# relay_AZ850P2_THT.net
KiCad netlist of a schematic drawn in EAGLE
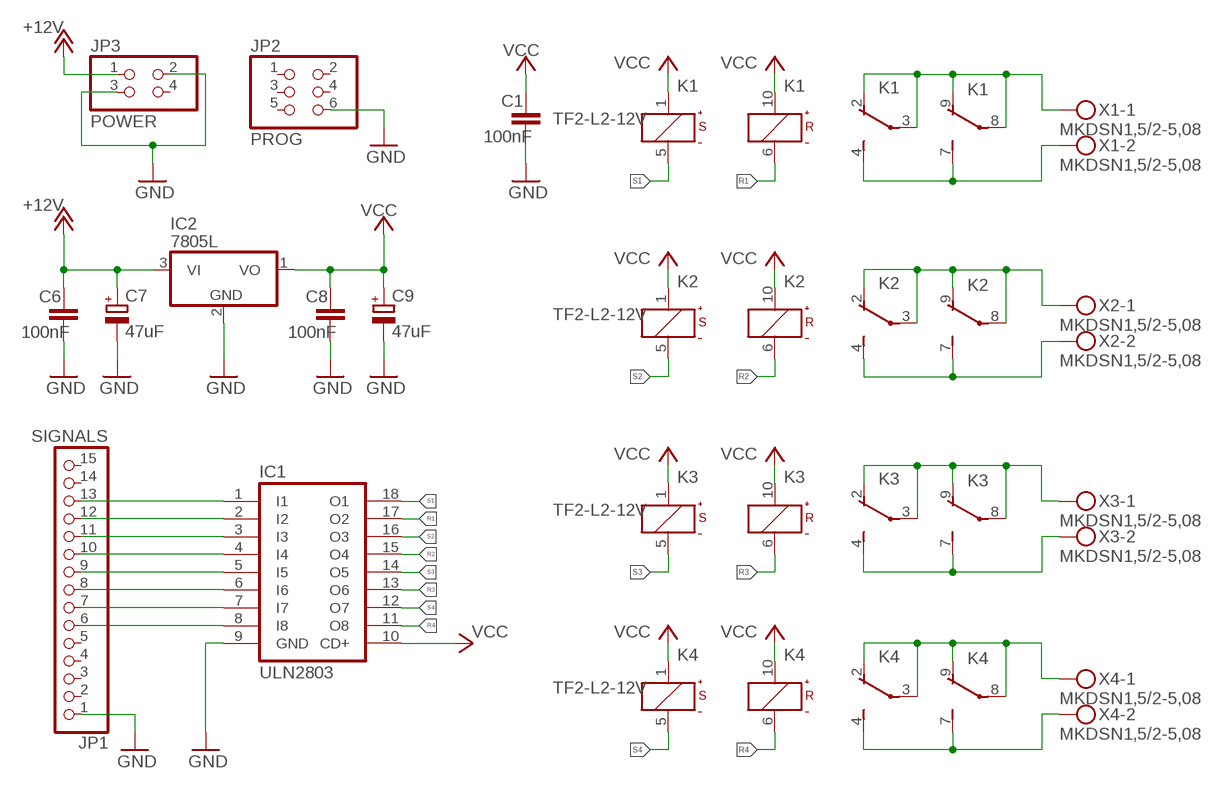
[diagram p0: schematic, sheet 1]

(export (version "E")
  (design (tool "Eeschema 10.0.6"))
  (components
    (comp (ref "C1")
      (value "100nF")
      (footprint "eagle-import:C025-025X050")
      (libsource (lib "eagle-import") (part "C-EU025-025X050"))
    )
    (comp (ref "C6")
      (value "100nF")
      (footprint "eagle-import:C025-025X050")
      (libsource (lib "eagle-import") (part "C-EU025-025X050"))
    )
    (comp (ref "C7")
      (value "47uF")
      (footprint "eagle-import:E2,5-6")
      (libsource (lib "eagle-import") (part "CPOL-EUE2.5-6"))
    )
    (comp (ref "C8")
      (value "100nF")
      (footprint "eagle-import:C025-025X050")
      (libsource (lib "eagle-import") (part "C-EU025-025X050"))
    )
    (comp (ref "C9")
      (value "47uF")
      (footprint "eagle-import:E2,5-6")
      (libsource (lib "eagle-import") (part "CPOL-EUE2.5-6"))
    )
    (comp (ref "IC1")
      (value "ULN2803")
      (footprint "eagle-import:DIL18")
      (libsource (lib "eagle-import") (part "ULN2803A"))
    )
    (comp (ref "IC2")
      (value "7805L")
      (footprint "eagle-import:TO92")
      (libsource (lib "eagle-import") (part "78L05"))
    )
    (comp (ref "JP1")
      (value "SIGNALS")
      (footprint "eagle-import:1X15")
      (libsource (lib "eagle-import") (part "PINHD-1X15"))
    )
    (comp (ref "JP2")
      (value "PROG")
      (footprint "eagle-import:2X03")
      (libsource (lib "eagle-import") (part "PINHD-2X3"))
    )
    (comp (ref "JP3")
      (value "POWER")
      (footprint "eagle-import:2X02")
      (libsource (lib "eagle-import") (part "PINHD-2X2"))
    )
    (comp (ref "K1")
      (value "TF2-L2-12V")
      (footprint "eagle-import:TF2")
      (libsource (lib "eagle-import") (part "TF2-L2-12V"))
    )
    (comp (ref "K2")
      (value "TF2-L2-12V")
      (footprint "eagle-import:TF2")
      (libsource (lib "eagle-import") (part "TF2-L2-12V"))
    )
    (comp (ref "K3")
      (value "TF2-L2-12V")
      (footprint "eagle-import:TF2")
      (libsource (lib "eagle-import") (part "TF2-L2-12V"))
    )
    (comp (ref "K4")
      (value "TF2-L2-12V")
      (footprint "eagle-import:TF2")
      (libsource (lib "eagle-import") (part "TF2-L2-12V"))
    )
    (comp (ref "X1")
      (value "MKDSN1,5/2-5,08")
      (footprint "eagle-import:MKDSN1,5_2-5,08")
      (fields (field (name "MPN") "MKDSN 1,5/2-5.08"))
      (libsource (lib "eagle-import") (part "MKDSN1,5/2-5,08"))
    )
    (comp (ref "X2")
      (value "MKDSN1,5/2-5,08")
      (footprint "eagle-import:MKDSN1,5_2-5,08")
      (fields (field (name "MPN") "MKDSN 1,5/2-5.08"))
      (libsource (lib "eagle-import") (part "MKDSN1,5/2-5,08"))
    )
    (comp (ref "X3")
      (value "MKDSN1,5/2-5,08")
      (footprint "eagle-import:MKDSN1,5_2-5,08")
      (fields (field (name "MPN") "MKDSN 1,5/2-5.08"))
      (libsource (lib "eagle-import") (part "MKDSN1,5/2-5,08"))
    )
    (comp (ref "X4")
      (value "MKDSN1,5/2-5,08")
      (footprint "eagle-import:MKDSN1,5_2-5,08")
      (fields (field (name "MPN") "MKDSN 1,5/2-5.08"))
      (libsource (lib "eagle-import") (part "MKDSN1,5/2-5,08"))
    )
  )
  (nets
    (net (code "1") (name "+12V") (class "Default")
      (node (ref "C6") (pin "1") (pinfunction "1_1") (pintype "passive"))
      (node (ref "C7") (pin "+") (pinfunction "+_+") (pintype "passive"))
      (node (ref "IC2") (pin "3") (pinfunction "VI_3") (pintype "input"))
      (node (ref "JP3") (pin "1") (pinfunction "1_1") (pintype "passive"))
    )
    (net (code "2") (name "GND") (class "Default")
      (node (ref "C1") (pin "2") (pinfunction "2_2") (pintype "passive"))
      (node (ref "C6") (pin "2") (pinfunction "2_2") (pintype "passive"))
      (node (ref "C7") (pin "-") (pinfunction "-_-") (pintype "passive"))
      (node (ref "C8") (pin "2") (pinfunction "2_2") (pintype "passive"))
      (node (ref "C9") (pin "-") (pinfunction "-_-") (pintype "passive"))
      (node (ref "IC1") (pin "9") (pinfunction "GND_9") (pintype "power_in"))
      (node (ref "IC2") (pin "2") (pinfunction "GND_2") (pintype "passive"))
      (node (ref "JP1") (pin "1") (pinfunction "1_1") (pintype "passive"))
      (node (ref "JP2") (pin "6") (pinfunction "6_6") (pintype "passive"))
      (node (ref "JP3") (pin "2") (pinfunction "2_2") (pintype "passive"))
      (node (ref "JP3") (pin "3") (pinfunction "3_3") (pintype "passive"))
    )
    (net (code "3") (name "Net-(IC1-I1)") (class "Default")
      (node (ref "IC1") (pin "1") (pinfunction "I1_1") (pintype "input"))
      (node (ref "JP1") (pin "13") (pinfunction "13_13") (pintype "passive"))
    )
    (net (code "4") (name "Net-(IC1-I2)") (class "Default")
      (node (ref "IC1") (pin "2") (pinfunction "I2_2") (pintype "input"))
      (node (ref "JP1") (pin "12") (pinfunction "12_12") (pintype "passive"))
    )
    (net (code "5") (name "Net-(IC1-I3)") (class "Default")
      (node (ref "IC1") (pin "3") (pinfunction "I3_3") (pintype "input"))
      (node (ref "JP1") (pin "11") (pinfunction "11_11") (pintype "passive"))
    )
    (net (code "6") (name "Net-(IC1-I4)") (class "Default")
      (node (ref "IC1") (pin "4") (pinfunction "I4_4") (pintype "input"))
      (node (ref "JP1") (pin "10") (pinfunction "10_10") (pintype "passive"))
    )
    (net (code "7") (name "Net-(IC1-I5)") (class "Default")
      (node (ref "IC1") (pin "5") (pinfunction "I5_5") (pintype "input"))
      (node (ref "JP1") (pin "9") (pinfunction "9_9") (pintype "passive"))
    )
    (net (code "8") (name "Net-(IC1-I6)") (class "Default")
      (node (ref "IC1") (pin "6") (pinfunction "I6_6") (pintype "input"))
      (node (ref "JP1") (pin "8") (pinfunction "8_8") (pintype "passive"))
    )
    (net (code "9") (name "Net-(IC1-I7)") (class "Default")
      (node (ref "IC1") (pin "7") (pinfunction "I7_7") (pintype "input"))
      (node (ref "JP1") (pin "7") (pinfunction "7_7") (pintype "passive"))
    )
    (net (code "10") (name "Net-(IC1-I8)") (class "Default")
      (node (ref "IC1") (pin "8") (pinfunction "I8_8") (pintype "input"))
      (node (ref "JP1") (pin "6") (pinfunction "6_6") (pintype "passive"))
    )
    (net (code "11") (name "Net-(K1A-O)") (class "Default")
      (node (ref "K1") (pin "2") (pinfunction "O_2") (pintype "passive"))
      (node (ref "K1") (pin "3") (pinfunction "P_3") (pintype "passive"))
      (node (ref "K1") (pin "8") (pinfunction "P_8") (pintype "passive"))
      (node (ref "K1") (pin "9") (pinfunction "O_9") (pintype "passive"))
      (node (ref "X1") (pin "1") (pinfunction "KL_1") (pintype "passive"))
    )
    (net (code "12") (name "Net-(K1A-S)") (class "Default")
      (node (ref "K1") (pin "4") (pinfunction "S_4") (pintype "passive"))
      (node (ref "K1") (pin "7") (pinfunction "S_7") (pintype "passive"))
      (node (ref "X1") (pin "2") (pinfunction "KL_2") (pintype "passive"))
    )
    (net (code "13") (name "Net-(K2A-O)") (class "Default")
      (node (ref "K2") (pin "2") (pinfunction "O_2") (pintype "passive"))
      (node (ref "K2") (pin "3") (pinfunction "P_3") (pintype "passive"))
      (node (ref "K2") (pin "8") (pinfunction "P_8") (pintype "passive"))
      (node (ref "K2") (pin "9") (pinfunction "O_9") (pintype "passive"))
      (node (ref "X2") (pin "1") (pinfunction "KL_1") (pintype "passive"))
    )
    (net (code "14") (name "Net-(K2A-S)") (class "Default")
      (node (ref "K2") (pin "4") (pinfunction "S_4") (pintype "passive"))
      (node (ref "K2") (pin "7") (pinfunction "S_7") (pintype "passive"))
      (node (ref "X2") (pin "2") (pinfunction "KL_2") (pintype "passive"))
    )
    (net (code "15") (name "Net-(K3A-O)") (class "Default")
      (node (ref "K3") (pin "2") (pinfunction "O_2") (pintype "passive"))
      (node (ref "K3") (pin "3") (pinfunction "P_3") (pintype "passive"))
      (node (ref "K3") (pin "8") (pinfunction "P_8") (pintype "passive"))
      (node (ref "K3") (pin "9") (pinfunction "O_9") (pintype "passive"))
      (node (ref "X3") (pin "1") (pinfunction "KL_1") (pintype "passive"))
    )
    (net (code "16") (name "Net-(K3A-S)") (class "Default")
      (node (ref "K3") (pin "4") (pinfunction "S_4") (pintype "passive"))
      (node (ref "K3") (pin "7") (pinfunction "S_7") (pintype "passive"))
      (node (ref "X3") (pin "2") (pinfunction "KL_2") (pintype "passive"))
    )
    (net (code "17") (name "Net-(K4A-O)") (class "Default")
      (node (ref "K4") (pin "2") (pinfunction "O_2") (pintype "passive"))
      (node (ref "K4") (pin "3") (pinfunction "P_3") (pintype "passive"))
      (node (ref "K4") (pin "8") (pinfunction "P_8") (pintype "passive"))
      (node (ref "K4") (pin "9") (pinfunction "O_9") (pintype "passive"))
      (node (ref "X4") (pin "1") (pinfunction "KL_1") (pintype "passive"))
    )
    (net (code "18") (name "Net-(K4A-S)") (class "Default")
      (node (ref "K4") (pin "4") (pinfunction "S_4") (pintype "passive"))
      (node (ref "K4") (pin "7") (pinfunction "S_7") (pintype "passive"))
      (node (ref "X4") (pin "2") (pinfunction "KL_2") (pintype "passive"))
    )
    (net (code "19") (name "R1") (class "Default")
      (node (ref "IC1") (pin "17") (pinfunction "O2_17") (pintype "open_collector"))
      (node (ref "K1") (pin "6") (pinfunction "-_6") (pintype "passive"))
    )
    (net (code "20") (name "R2") (class "Default")
      (node (ref "IC1") (pin "15") (pinfunction "O4_15") (pintype "open_collector"))
      (node (ref "K2") (pin "6") (pinfunction "-_6") (pintype "passive"))
    )
    (net (code "21") (name "R3") (class "Default")
      (node (ref "IC1") (pin "13") (pinfunction "O6_13") (pintype "open_collector"))
      (node (ref "K3") (pin "6") (pinfunction "-_6") (pintype "passive"))
    )
    (net (code "22") (name "R4") (class "Default")
      (node (ref "IC1") (pin "11") (pinfunction "O8_11") (pintype "open_collector"))
      (node (ref "K4") (pin "6") (pinfunction "-_6") (pintype "passive"))
    )
    (net (code "23") (name "S1") (class "Default")
      (node (ref "IC1") (pin "18") (pinfunction "O1_18") (pintype "open_collector"))
      (node (ref "K1") (pin "5") (pinfunction "-_5") (pintype "passive"))
    )
    (net (code "24") (name "S2") (class "Default")
      (node (ref "IC1") (pin "16") (pinfunction "O3_16") (pintype "open_collector"))
      (node (ref "K2") (pin "5") (pinfunction "-_5") (pintype "passive"))
    )
    (net (code "25") (name "S3") (class "Default")
      (node (ref "IC1") (pin "14") (pinfunction "O5_14") (pintype "open_collector"))
      (node (ref "K3") (pin "5") (pinfunction "-_5") (pintype "passive"))
    )
    (net (code "26") (name "S4") (class "Default")
      (node (ref "IC1") (pin "12") (pinfunction "O7_12") (pintype "open_collector"))
      (node (ref "K4") (pin "5") (pinfunction "-_5") (pintype "passive"))
    )
    (net (code "27") (name "VCC") (class "Default")
      (node (ref "C1") (pin "1") (pinfunction "1_1") (pintype "passive"))
      (node (ref "C8") (pin "1") (pinfunction "1_1") (pintype "passive"))
      (node (ref "C9") (pin "+") (pinfunction "+_+") (pintype "passive"))
      (node (ref "IC1") (pin "10") (pinfunction "CD+_10") (pintype "passive"))
      (node (ref "IC2") (pin "1") (pinfunction "VO_1") (pintype "passive"))
      (node (ref "K1") (pin "1") (pinfunction "+_1") (pintype "passive"))
      (node (ref "K1") (pin "10") (pinfunction "+_10") (pintype "passive"))
      (node (ref "K2") (pin "1") (pinfunction "+_1") (pintype "passive"))
      (node (ref "K2") (pin "10") (pinfunction "+_10") (pintype "passive"))
      (node (ref "K3") (pin "1") (pinfunction "+_1") (pintype "passive"))
      (node (ref "K3") (pin "10") (pinfunction "+_10") (pintype "passive"))
      (node (ref "K4") (pin "1") (pinfunction "+_1") (pintype "passive"))
      (node (ref "K4") (pin "10") (pinfunction "+_10") (pintype "passive"))
    )
    (net (code "28") (name "unconnected-(JP1-Pad2)") (class "Default")
      (node (ref "JP1") (pin "2") (pinfunction "2_2") (pintype "passive"))
    )
    (net (code "29") (name "unconnected-(JP1-Pad3)") (class "Default")
      (node (ref "JP1") (pin "3") (pinfunction "3_3") (pintype "passive"))
    )
    (net (code "30") (name "unconnected-(JP1-Pad4)") (class "Default")
      (node (ref "JP1") (pin "4") (pinfunction "4_4") (pintype "passive"))
    )
    (net (code "31") (name "unconnected-(JP1-Pad5)") (class "Default")
      (node (ref "JP1") (pin "5") (pinfunction "5_5") (pintype "passive"))
    )
    (net (code "32") (name "unconnected-(JP1-Pad14)") (class "Default")
      (node (ref "JP1") (pin "14") (pinfunction "14_14") (pintype "passive"))
    )
    (net (code "33") (name "unconnected-(JP1-Pad15)") (class "Default")
      (node (ref "JP1") (pin "15") (pinfunction "15_15") (pintype "passive"))
    )
    (net (code "34") (name "unconnected-(JP2-Pad1)") (class "Default")
      (node (ref "JP2") (pin "1") (pinfunction "1_1") (pintype "passive"))
    )
    (net (code "35") (name "unconnected-(JP2-Pad2)") (class "Default")
      (node (ref "JP2") (pin "2") (pinfunction "2_2") (pintype "passive"))
    )
    (net (code "36") (name "unconnected-(JP2-Pad3)") (class "Default")
      (node (ref "JP2") (pin "3") (pinfunction "3_3") (pintype "passive"))
    )
    (net (code "37") (name "unconnected-(JP2-Pad4)") (class "Default")
      (node (ref "JP2") (pin "4") (pinfunction "4_4") (pintype "passive"))
    )
    (net (code "38") (name "unconnected-(JP2-Pad5)") (class "Default")
      (node (ref "JP2") (pin "5") (pinfunction "5_5") (pintype "passive"))
    )
    (net (code "39") (name "unconnected-(JP3-Pad4)") (class "Default")
      (node (ref "JP3") (pin "4") (pinfunction "4_4") (pintype "passive"))
    )
  )
)
